# Pomiar-Energii_A4_Landscape.net
KiCad netlist of a schematic drawn in Altium Designer
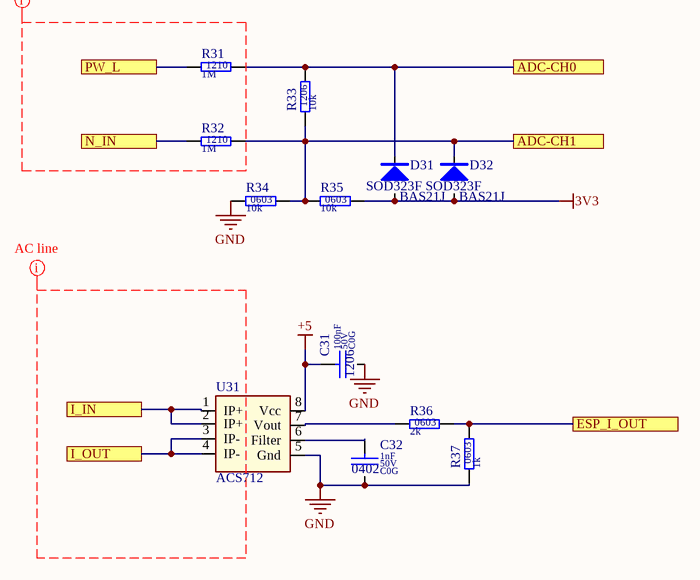
[diagram p0: Pomiar-Energii_A4_Landscape_.SchDoc]

(export (version "E")
  (design (tool "Eeschema 10.0.6"))
  (components
    (comp (ref "C31")
      (value "100nF")
      (footprint "C_1206_3216")
      (description "Capacitor")
      (fields
        (field (name "DIELECTRIC") "C0G")
        (field (name "VOLTAGE") "50V")
        (field (name "SCH_FOOTPRINT") "1206")
        (field (name "PART NUMBER") "C_100nF_50V_C0G_1206_5")
        (field (name "MANUFACTURER") "Walsin")
      )
      (libsource (lib "Library") (part "C"))
    )
    (comp (ref "C32")
      (value "1nF")
      (footprint "C_0402_1005")
      (description "Capacitor")
      (fields
        (field (name "DIELECTRIC") "C0G")
        (field (name "VOLTAGE") "50V")
        (field (name "SCH_FOOTPRINT") "0402")
        (field (name "PART NUMBER") "C_1nF_50V_C0G_0402_5")
        (field (name "MANUFACTURER") "Murata")
      )
      (libsource (lib "Library") (part "C"))
    )
    (comp (ref "D31")
      (value "BAS21J")
      (footprint "SOD323F")
      (fields
        (field (name "SCH_FOOTPRINT") "SOD323F")
        (field (name "PART NUMBER") "D_BAS21J_0A25_300V_SOD323F")
        (field (name "VOLTAGE") "300V")
        (field (name "MANUFACTURER") "nexperia")
      )
      (libsource (lib "Library") (part "D"))
    )
    (comp (ref "D32")
      (value "BAS21J")
      (footprint "SOD323F")
      (fields
        (field (name "SCH_FOOTPRINT") "SOD323F")
        (field (name "PART NUMBER") "D_BAS21J_0A25_300V_SOD323F")
        (field (name "VOLTAGE") "300V")
        (field (name "MANUFACTURER") "nexperia")
      )
      (libsource (lib "Library") (part "D"))
    )
    (comp (ref "R31")
      (value "1M")
      (footprint "R_1210_3225")
      (fields
        (field (name "SCH_FOOTPRINT") "1210")
        (field (name "PART NUMBER") "R_1M_1210_1")
        (field (name "VOLTAGE") "200V")
        (field (name "POWER") "500mW")
      )
      (libsource (lib "Library") (part "R"))
    )
    (comp (ref "R32")
      (value "1M")
      (footprint "R_1210_3225")
      (fields
        (field (name "SCH_FOOTPRINT") "1210")
        (field (name "PART NUMBER") "R_1M_1210_1")
        (field (name "VOLTAGE") "200V")
        (field (name "POWER") "500mW")
      )
      (libsource (lib "Library") (part "R"))
    )
    (comp (ref "R33")
      (value "10k")
      (footprint "R_1206_3216")
      (fields
        (field (name "SCH_FOOTPRINT") "1206")
        (field (name "PART NUMBER") "R_10k_1206_1")
        (field (name "VOLTAGE") "200V")
        (field (name "POWER") "125mW")
      )
      (libsource (lib "Library") (part "R"))
    )
    (comp (ref "R34")
      (value "10k")
      (footprint "R_0603_1608")
      (fields
        (field (name "SCH_FOOTPRINT") "0603")
        (field (name "PART NUMBER") "R_10k_0603_1")
        (field (name "VOLTAGE") "75V")
        (field (name "POWER") "100mW")
      )
      (libsource (lib "Library") (part "R"))
    )
    (comp (ref "R35")
      (value "10k")
      (footprint "R_0603_1608")
      (fields
        (field (name "SCH_FOOTPRINT") "0603")
        (field (name "PART NUMBER") "R_10k_0603_1")
        (field (name "VOLTAGE") "75V")
        (field (name "POWER") "100mW")
      )
      (libsource (lib "Library") (part "R"))
    )
    (comp (ref "R36")
      (value "2k")
      (footprint "R_0603_1608")
      (fields
        (field (name "SCH_FOOTPRINT") "0603")
        (field (name "PART NUMBER") "R_2k_0603")
        (field (name "POWER") "100mW")
        (field (name "TOLERANCE") "1%")
      )
      (libsource (lib "Library") (part "R"))
    )
    (comp (ref "R37")
      (value "1k")
      (footprint "R_0603_1608")
      (fields
        (field (name "SCH_FOOTPRINT") "0603")
        (field (name "PART NUMBER") "R_2k_0603")
        (field (name "POWER") "100mW")
        (field (name "TOLERANCE") "1%")
      )
      (libsource (lib "Library") (part "R"))
    )
    (comp (ref "U31")
      (value "ACS712")
      (footprint "ACS712")
      (libsource (lib "Integrated_Library1") (part "ACS712"))
    )
  )
  (nets
    (net (code "1") (name "+5") (class "Default")
      (node (ref "C31") (pin "1") (pinfunction "1_1") (pintype "passive"))
      (node (ref "U31") (pin "8") (pinfunction "Vcc_8") (pintype "passive"))
    )
    (net (code "2") (name "/ADC-CH0") (class "Default")
      (node (ref "D31") (pin "1") (pintype "passive"))
      (node (ref "R31") (pin "2") (pinfunction "2_2") (pintype "passive"))
      (node (ref "R33") (pin "2") (pinfunction "2_2") (pintype "passive"))
    )
    (net (code "3") (name "/ADC-CH1") (class "Default")
      (node (ref "D32") (pin "1") (pintype "passive"))
      (node (ref "R32") (pin "2") (pinfunction "2_2") (pintype "passive"))
      (node (ref "R33") (pin "1") (pinfunction "1_1") (pintype "passive"))
      (node (ref "R34") (pin "2") (pinfunction "2_2") (pintype "passive"))
      (node (ref "R35") (pin "1") (pinfunction "1_1") (pintype "passive"))
    )
    (net (code "4") (name "/ESP_I_OUT") (class "Default")
      (node (ref "R36") (pin "2") (pinfunction "2_2") (pintype "passive"))
      (node (ref "R37") (pin "2") (pinfunction "2_2") (pintype "passive"))
    )
    (net (code "5") (name "/I_IN") (class "Default")
      (node (ref "U31") (pin "1") (pinfunction "IP+_1") (pintype "passive"))
      (node (ref "U31") (pin "2") (pinfunction "IP+_2") (pintype "passive"))
    )
    (net (code "6") (name "/I_OUT") (class "Default")
      (node (ref "U31") (pin "3") (pinfunction "IP-_3") (pintype "passive"))
      (node (ref "U31") (pin "4") (pinfunction "IP-_4") (pintype "passive"))
    )
    (net (code "7") (name "/N_IN") (class "Default")
      (node (ref "R32") (pin "1") (pinfunction "1_1") (pintype "passive"))
    )
    (net (code "8") (name "/PW_L") (class "Default")
      (node (ref "R31") (pin "1") (pinfunction "1_1") (pintype "passive"))
    )
    (net (code "9") (name "3V3") (class "Default")
      (node (ref "D31") (pin "2") (pintype "passive"))
      (node (ref "D32") (pin "2") (pintype "passive"))
      (node (ref "R35") (pin "2") (pinfunction "2_2") (pintype "passive"))
    )
    (net (code "10") (name "GND") (class "Default")
      (node (ref "C31") (pin "2") (pinfunction "2_2") (pintype "passive"))
      (node (ref "C32") (pin "2") (pinfunction "2_2") (pintype "passive"))
      (node (ref "R34") (pin "1") (pinfunction "1_1") (pintype "passive"))
      (node (ref "R37") (pin "1") (pinfunction "1_1") (pintype "passive"))
      (node (ref "U31") (pin "5") (pinfunction "Gnd_5") (pintype "passive"))
    )
    (net (code "11") (name "Net-(U31-Filter)") (class "Default")
      (node (ref "C32") (pin "1") (pinfunction "1_1") (pintype "passive"))
      (node (ref "U31") (pin "6") (pinfunction "Filter_6") (pintype "passive"))
    )
    (net (code "12") (name "Net-(U31-Vout)") (class "Default")
      (node (ref "R36") (pin "1") (pinfunction "1_1") (pintype "passive"))
      (node (ref "U31") (pin "7") (pinfunction "Vout_7") (pintype "passive"))
    )
  )
)
